# ozino_xyz_blue.net
KiCad netlist of a schematic drawn in EAGLE
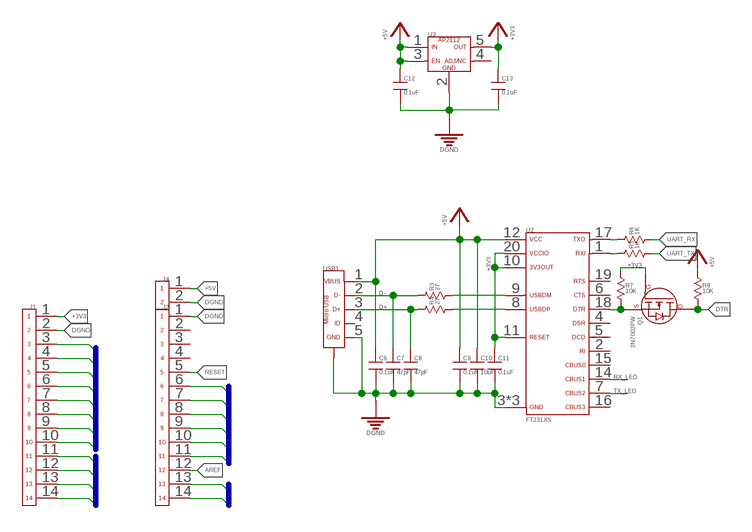
[diagram p0: schematic, sheet 1, part 1 of 2]
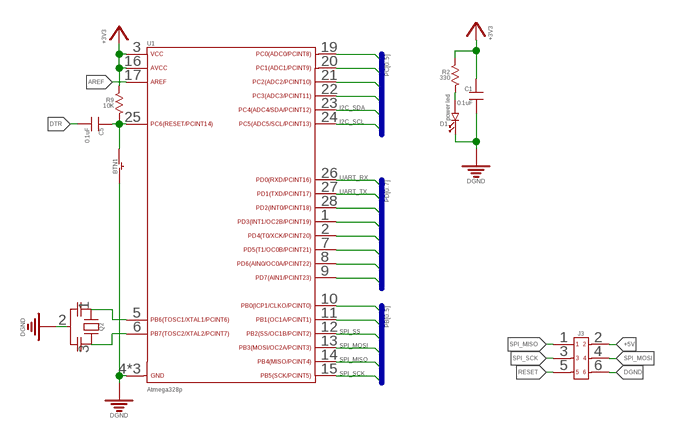
[diagram p1: schematic, sheet 1, part 2 of 2]

(export (version "E")
  (design (tool "Eeschema 10.0.6"))
  (components
    (comp (ref "BTN1")
      (value "BTN_NORMAL_OFF_6_3.5_SMD")
      (footprint "eagle-import:BTN_6_3.5_SMD")
      (libsource (lib "eagle-import") (part "BTN_NORMAL_OFF_6_3.5_SMD"))
    )
    (comp (ref "C1")
      (value "0.1uF")
      (footprint "eagle-import:0402")
      (libsource (lib "eagle-import") (part "CAPACITOR_FIXED_0402"))
    )
    (comp (ref "C5")
      (value "0.1uF")
      (footprint "eagle-import:0402")
      (libsource (lib "eagle-import") (part "CAPACITOR_FIXED_0402"))
    )
    (comp (ref "C6")
      (value "0.1uF")
      (footprint "eagle-import:0402")
      (libsource (lib "eagle-import") (part "CAPACITOR_FIXED_0402"))
    )
    (comp (ref "C7")
      (value "47pF")
      (footprint "eagle-import:0402")
      (libsource (lib "eagle-import") (part "CAPACITOR_FIXED_0402"))
    )
    (comp (ref "C8")
      (value "47pF")
      (footprint "eagle-import:0402")
      (libsource (lib "eagle-import") (part "CAPACITOR_FIXED_0402"))
    )
    (comp (ref "C9")
      (value "0.1uF")
      (footprint "eagle-import:0402")
      (libsource (lib "eagle-import") (part "CAPACITOR_FIXED_0402"))
    )
    (comp (ref "C10")
      (value "10uF")
      (footprint "eagle-import:0402")
      (libsource (lib "eagle-import") (part "CAPACITOR_FIXED_0402"))
    )
    (comp (ref "C11")
      (value "0.1uF")
      (footprint "eagle-import:0402")
      (libsource (lib "eagle-import") (part "CAPACITOR_FIXED_0402"))
    )
    (comp (ref "C12")
      (value "0.1uF")
      (footprint "eagle-import:0402")
      (libsource (lib "eagle-import") (part "CAPACITOR_FIXED_0402"))
    )
    (comp (ref "C13")
      (value "0.1uF")
      (footprint "eagle-import:0402")
      (libsource (lib "eagle-import") (part "CAPACITOR_FIXED_0402"))
    )
    (comp (ref "D1")
      (value "power led")
      (footprint "eagle-import:0805DIODE")
      (libsource (lib "eagle-import") (part "LED-0805"))
    )
    (comp (ref "J1")
      (value "14PIN_HEADER_PITCH2.54MM_TH")
      (footprint "eagle-import:14PIN_HEADER_PITCH2.54MM_TH")
      (libsource (lib "eagle-import") (part "14PIN_HEADER_PITCH2.54MM_TH"))
    )
    (comp (ref "J2")
      (value "14PIN_HEADER_PITCH2.54MM_TH")
      (footprint "eagle-import:14PIN_HEADER_PITCH2.54MM_TH")
      (libsource (lib "eagle-import") (part "14PIN_HEADER_PITCH2.54MM_TH"))
    )
    (comp (ref "J3")
      (value "6PIN_2ROW_TC2030_NL")
      (footprint "eagle-import:TC2030_NL")
      (libsource (lib "eagle-import") (part "6PIN_2ROW_TC2030_NL"))
    )
    (comp (ref "J4")
      (value "2PIN_HEADER_PITCH2.54MM_TH")
      (footprint "eagle-import:2PIN_HEADER_PITCH2.54MM_TH")
      (libsource (lib "eagle-import") (part "2PIN_HEADER_PITCH2.54MM_TH"))
    )
    (comp (ref "Q1")
      (value "2N7002PW")
      (footprint "eagle-import:SOT323(SC-70)")
      (libsource (lib "eagle-import") (part "2N7002PW"))
    )
    (comp (ref "Q2")
      (value "RESONATORS")
      (footprint "eagle-import:CXTCE_____V")
      (libsource (lib "eagle-import") (part "RESONATORS"))
    )
    (comp (ref "R2")
      (value "330")
      (footprint "eagle-import:0805")
      (libsource (lib "eagle-import") (part "RESISTOR_0805"))
    )
    (comp (ref "R3")
      (value "27")
      (footprint "eagle-import:0402")
      (libsource (lib "eagle-import") (part "RESISTOR_0402"))
    )
    (comp (ref "R4")
      (value "27")
      (footprint "eagle-import:0402")
      (libsource (lib "eagle-import") (part "RESISTOR_0402"))
    )
    (comp (ref "R5")
      (value "1K")
      (footprint "eagle-import:0402")
      (libsource (lib "eagle-import") (part "RESISTOR_0402"))
    )
    (comp (ref "R6")
      (value "1K")
      (footprint "eagle-import:0402")
      (libsource (lib "eagle-import") (part "RESISTOR_0402"))
    )
    (comp (ref "R7")
      (value "10K")
      (footprint "eagle-import:0402")
      (libsource (lib "eagle-import") (part "RESISTOR_0402"))
    )
    (comp (ref "R8")
      (value "10K")
      (footprint "eagle-import:0402")
      (libsource (lib "eagle-import") (part "RESISTOR_0402"))
    )
    (comp (ref "R9")
      (value "10K")
      (footprint "eagle-import:0402")
      (libsource (lib "eagle-import") (part "RESISTOR_0402"))
    )
    (comp (ref "U1")
      (value "Atmega328p")
      (footprint "eagle-import:QFN-28")
      (libsource (lib "eagle-import") (part "ATMEGA48A/PA/88A/PA/168A/PA/328/P(28PIN)_28QFN"))
    )
    (comp (ref "U2")
      (value "FT231XS_WFQFN20")
      (footprint "eagle-import:WFQFN-20")
      (libsource (lib "eagle-import") (part "FT231XS_WFQFN20"))
    )
    (comp (ref "U3")
      (value "AP2112K_SOT-23-5")
      (footprint "eagle-import:SOT-23-5")
      (libsource (lib "eagle-import") (part "AP2112K_SOT-23-5"))
    )
    (comp (ref "USB1")
      (value "USB-2.0-MICRO_SMD_SMD")
      (footprint "eagle-import:MICRO-USB-B-SMD-SMD")
      (libsource (lib "eagle-import") (part "USB-2.0-MICRO_SMD_SMD"))
    )
  )
  (nets
    (net (code "9") (name "+3V3") (class "Default")
      (node (ref "C1") (pin "1") (pinfunction "1_1") (pintype "passive"))
      (node (ref "C11") (pin "1") (pinfunction "1_1") (pintype "passive"))
      (node (ref "C13") (pin "1") (pinfunction "1_1") (pintype "passive"))
      (node (ref "J1") (pin "1") (pinfunction "1_1") (pintype "passive"))
      (node (ref "Q1") (pin "1") (pinfunction "G_1") (pintype "passive"))
      (node (ref "R2") (pin "1") (pinfunction "1_1") (pintype "passive"))
      (node (ref "R7") (pin "1") (pinfunction "1_1") (pintype "passive"))
      (node (ref "R9") (pin "1") (pinfunction "1_1") (pintype "passive"))
      (node (ref "U1") (pin "16") (pinfunction "AVCC_16") (pintype "passive"))
      (node (ref "U1") (pin "3") (pinfunction "VCC_3") (pintype "passive"))
      (node (ref "U2") (pin "10") (pinfunction "3V3OUT_10") (pintype "passive"))
      (node (ref "U2") (pin "11") (pinfunction "RESET_11") (pintype "passive"))
      (node (ref "U2") (pin "20") (pinfunction "VCCIO_20") (pintype "passive"))
      (node (ref "U3") (pin "5") (pinfunction "5_5") (pintype "passive"))
    )
    (net (code "10") (name "+5V") (class "Default")
      (node (ref "C10") (pin "1") (pinfunction "1_1") (pintype "passive"))
      (node (ref "C12") (pin "1") (pinfunction "1_1") (pintype "passive"))
      (node (ref "C6") (pin "1") (pinfunction "1_1") (pintype "passive"))
      (node (ref "C9") (pin "1") (pinfunction "1_1") (pintype "passive"))
      (node (ref "J3") (pin "2") (pinfunction "2_2") (pintype "passive"))
      (node (ref "J4") (pin "1") (pinfunction "1_1") (pintype "passive"))
      (node (ref "R8") (pin "1") (pinfunction "1_1") (pintype "passive"))
      (node (ref "U2") (pin "12") (pinfunction "VCC_12") (pintype "passive"))
      (node (ref "U3") (pin "1") (pinfunction "1_1") (pintype "passive"))
      (node (ref "U3") (pin "3") (pinfunction "3_3") (pintype "passive"))
      (node (ref "USB1") (pin "1") (pinfunction "VBUS_1") (pintype "passive"))
    )
    (net (code "11") (name "/D+") (class "Default")
      (node (ref "C8") (pin "1") (pinfunction "1_1") (pintype "passive"))
      (node (ref "R4") (pin "1") (pinfunction "1_1") (pintype "passive"))
      (node (ref "USB1") (pin "3") (pinfunction "D+_3") (pintype "passive"))
    )
    (net (code "12") (name "/D-") (class "Default")
      (node (ref "C7") (pin "1") (pinfunction "1_1") (pintype "passive"))
      (node (ref "R3") (pin "1") (pinfunction "1_1") (pintype "passive"))
      (node (ref "USB1") (pin "2") (pinfunction "D-_2") (pintype "passive"))
    )
    (net (code "13") (name "/I2C_SCL") (class "Default")
      (node (ref "J2") (pin "6") (pinfunction "6_6") (pintype "passive"))
      (node (ref "U1") (pin "24") (pinfunction "PC5_24") (pintype "passive"))
    )
    (net (code "14") (name "/I2C_SDA") (class "Default")
      (node (ref "J2") (pin "7") (pinfunction "7_7") (pintype "passive"))
      (node (ref "U1") (pin "23") (pinfunction "PC4_23") (pintype "passive"))
    )
    (net (code "15") (name "/PB0") (class "Default")
      (node (ref "J1") (pin "11") (pinfunction "11_11") (pintype "passive"))
      (node (ref "U1") (pin "10") (pinfunction "PB0_10") (pintype "passive"))
    )
    (net (code "16") (name "/PB1") (class "Default")
      (node (ref "J1") (pin "12") (pinfunction "12_12") (pintype "passive"))
      (node (ref "U1") (pin "11") (pinfunction "PB1_11") (pintype "passive"))
    )
    (net (code "18") (name "/PC0") (class "Default")
      (node (ref "J2") (pin "11") (pinfunction "11_11") (pintype "passive"))
      (node (ref "U1") (pin "19") (pinfunction "PC0_19") (pintype "passive"))
    )
    (net (code "19") (name "/PC1") (class "Default")
      (node (ref "J2") (pin "10") (pinfunction "10_10") (pintype "passive"))
      (node (ref "U1") (pin "20") (pinfunction "PC1_20") (pintype "passive"))
    )
    (net (code "20") (name "/PC2") (class "Default")
      (node (ref "J2") (pin "9") (pinfunction "9_9") (pintype "passive"))
      (node (ref "U1") (pin "21") (pinfunction "PC2_21") (pintype "passive"))
    )
    (net (code "21") (name "/PC3") (class "Default")
      (node (ref "J2") (pin "8") (pinfunction "8_8") (pintype "passive"))
      (node (ref "U1") (pin "22") (pinfunction "PC3_22") (pintype "passive"))
    )
    (net (code "23") (name "/PD2") (class "Default")
      (node (ref "J1") (pin "5") (pinfunction "5_5") (pintype "passive"))
      (node (ref "U1") (pin "28") (pinfunction "PD2_28") (pintype "passive"))
    )
    (net (code "24") (name "/PD3") (class "Default")
      (node (ref "J1") (pin "6") (pinfunction "6_6") (pintype "passive"))
      (node (ref "U1") (pin "1") (pinfunction "PD3_1") (pintype "passive"))
    )
    (net (code "25") (name "/PD4") (class "Default")
      (node (ref "J1") (pin "7") (pinfunction "7_7") (pintype "passive"))
      (node (ref "U1") (pin "2") (pinfunction "PD4_2") (pintype "passive"))
    )
    (net (code "26") (name "/PD5") (class "Default")
      (node (ref "J1") (pin "8") (pinfunction "8_8") (pintype "passive"))
      (node (ref "U1") (pin "7") (pinfunction "PD5_7") (pintype "passive"))
    )
    (net (code "27") (name "/PD6") (class "Default")
      (node (ref "J1") (pin "9") (pinfunction "9_9") (pintype "passive"))
      (node (ref "U1") (pin "8") (pinfunction "PD6_8") (pintype "passive"))
    )
    (net (code "28") (name "/PD7") (class "Default")
      (node (ref "J1") (pin "10") (pinfunction "10_10") (pintype "passive"))
      (node (ref "U1") (pin "9") (pinfunction "PD7_9") (pintype "passive"))
    )
    (net (code "30") (name "/RX_LED") (class "Default")
      (node (ref "U2") (pin "14") (pinfunction "CBUS1_14") (pintype "passive"))
    )
    (net (code "31") (name "/SPI_SS") (class "Default")
      (node (ref "J1") (pin "13") (pinfunction "13_13") (pintype "passive"))
      (node (ref "U1") (pin "12") (pinfunction "PB2_12") (pintype "passive"))
    )
    (net (code "32") (name "/TX_LED") (class "Default")
      (node (ref "U2") (pin "7") (pinfunction "CBUS2_7") (pintype "passive"))
    )
    (net (code "33") (name "AREF") (class "Default")
      (node (ref "J2") (pin "12") (pinfunction "12_12") (pintype "passive"))
      (node (ref "U1") (pin "17") (pinfunction "AREF_17") (pintype "passive"))
    )
    (net (code "34") (name "DGND") (class "Default")
      (node (ref "BTN1") (pin "1") (pinfunction "1_1") (pintype "passive"))
      (node (ref "C1") (pin "2") (pinfunction "2_2") (pintype "passive"))
      (node (ref "C10") (pin "2") (pinfunction "2_2") (pintype "passive"))
      (node (ref "C11") (pin "2") (pinfunction "2_2") (pintype "passive"))
      (node (ref "C12") (pin "2") (pinfunction "2_2") (pintype "passive"))
      (node (ref "C13") (pin "2") (pinfunction "2_2") (pintype "passive"))
      (node (ref "C6") (pin "2") (pinfunction "2_2") (pintype "passive"))
      (node (ref "C7") (pin "2") (pinfunction "2_2") (pintype "passive"))
      (node (ref "C8") (pin "2") (pinfunction "2_2") (pintype "passive"))
      (node (ref "C9") (pin "2") (pinfunction "2_2") (pintype "passive"))
      (node (ref "D1") (pin "1") (pinfunction "K_1") (pintype "passive"))
      (node (ref "J1") (pin "2") (pinfunction "2_2") (pintype "passive"))
      (node (ref "J2") (pin "1") (pinfunction "1_1") (pintype "passive"))
      (node (ref "J3") (pin "6") (pinfunction "6_6") (pintype "passive"))
      (node (ref "J4") (pin "2") (pinfunction "2_2") (pintype "passive"))
      (node (ref "Q2") (pin "2") (pinfunction "2_2") (pintype "passive"))
      (node (ref "U1") (pin "18") (pinfunction "GND_18") (pintype "passive"))
      (node (ref "U1") (pin "4") (pinfunction "GND_4") (pintype "passive"))
      (node (ref "U1") (pin "T") (pinfunction "GND_T") (pintype "passive"))
      (node (ref "U2") (pin "13") (pinfunction "GND_13") (pintype "passive"))
      (node (ref "U2") (pin "3") (pinfunction "GND_3") (pintype "passive"))
      (node (ref "U2") (pin "T") (pinfunction "GND_T") (pintype "passive"))
      (node (ref "U3") (pin "2") (pinfunction "2_2") (pintype "passive"))
      (node (ref "USB1") (pin "5") (pinfunction "GND_5") (pintype "passive"))
      (node (ref "USB1") (pin "M1") (pinfunction "SHIELD_M1") (pintype "passive"))
      (node (ref "USB1") (pin "M2") (pinfunction "SHIELD_M2") (pintype "passive"))
      (node (ref "USB1") (pin "M3") (pinfunction "SHIELD_M3") (pintype "passive"))
      (node (ref "USB1") (pin "M4") (pinfunction "SHIELD_M4") (pintype "passive"))
      (node (ref "USB1") (pin "S1") (pinfunction "SHIELD_S1") (pintype "passive"))
      (node (ref "USB1") (pin "S2") (pinfunction "SHIELD_S2") (pintype "passive"))
    )
    (net (code "35") (name "DTR") (class "Default")
      (node (ref "C5") (pin "2") (pinfunction "2_2") (pintype "passive"))
      (node (ref "Q1") (pin "3") (pinfunction "D_3") (pintype "passive"))
      (node (ref "R8") (pin "2") (pinfunction "2_2") (pintype "passive"))
    )
    (net (code "36") (name "Net-(D1-A)") (class "Default")
      (node (ref "D1") (pin "2") (pinfunction "A_2") (pintype "passive"))
      (node (ref "R2") (pin "2") (pinfunction "2_2") (pintype "passive"))
    )
    (net (code "37") (name "Net-(Q1-S)") (class "Default")
      (node (ref "Q1") (pin "2") (pinfunction "S_2") (pintype "passive"))
      (node (ref "R7") (pin "2") (pinfunction "2_2") (pintype "passive"))
      (node (ref "U2") (pin "18") (pinfunction "DTR_18") (pintype "passive"))
    )
    (net (code "38") (name "Net-(U1-PB6)") (class "Default")
      (node (ref "Q2") (pin "1") (pinfunction "1_1") (pintype "passive"))
      (node (ref "U1") (pin "5") (pinfunction "PB6_5") (pintype "passive"))
    )
    (net (code "39") (name "Net-(U1-PB7)") (class "Default")
      (node (ref "Q2") (pin "3") (pinfunction "3_3") (pintype "passive"))
      (node (ref "U1") (pin "6") (pinfunction "PB7_6") (pintype "passive"))
    )
    (net (code "40") (name "Net-(U2-RXD)") (class "Default")
      (node (ref "R5") (pin "1") (pinfunction "1_1") (pintype "passive"))
      (node (ref "U2") (pin "1") (pinfunction "RXD_1") (pintype "passive"))
    )
    (net (code "41") (name "Net-(U2-TXD)") (class "Default")
      (node (ref "R6") (pin "1") (pinfunction "1_1") (pintype "passive"))
      (node (ref "U2") (pin "17") (pinfunction "TXD_17") (pintype "passive"))
    )
    (net (code "42") (name "Net-(U2-USBDM)") (class "Default")
      (node (ref "R3") (pin "2") (pinfunction "2_2") (pintype "passive"))
      (node (ref "U2") (pin "9") (pinfunction "USBDM_9") (pintype "passive"))
    )
    (net (code "43") (name "Net-(U2-USBDP)") (class "Default")
      (node (ref "R4") (pin "2") (pinfunction "2_2") (pintype "passive"))
      (node (ref "U2") (pin "8") (pinfunction "USBDP_8") (pintype "passive"))
    )
    (net (code "44") (name "RESET") (class "Default")
      (node (ref "BTN1") (pin "2") (pinfunction "2_2") (pintype "passive"))
      (node (ref "C5") (pin "1") (pinfunction "1_1") (pintype "passive"))
      (node (ref "J2") (pin "5") (pinfunction "5_5") (pintype "passive"))
      (node (ref "J3") (pin "5") (pinfunction "5_5") (pintype "passive"))
      (node (ref "R9") (pin "2") (pinfunction "2_2") (pintype "passive"))
      (node (ref "U1") (pin "25") (pinfunction "PC6_25") (pintype "passive"))
    )
    (net (code "45") (name "SPI_MISO") (class "Default")
      (node (ref "J2") (pin "14") (pinfunction "14_14") (pintype "passive"))
      (node (ref "J3") (pin "1") (pinfunction "1_1") (pintype "passive"))
      (node (ref "U1") (pin "14") (pinfunction "PB4_14") (pintype "passive"))
    )
    (net (code "46") (name "SPI_MOSI") (class "Default")
      (node (ref "J1") (pin "14") (pinfunction "14_14") (pintype "passive"))
      (node (ref "J3") (pin "4") (pinfunction "4_4") (pintype "passive"))
      (node (ref "U1") (pin "13") (pinfunction "PB3_13") (pintype "passive"))
    )
    (net (code "47") (name "SPI_SCK") (class "Default")
      (node (ref "J2") (pin "13") (pinfunction "13_13") (pintype "passive"))
      (node (ref "J3") (pin "3") (pinfunction "3_3") (pintype "passive"))
      (node (ref "U1") (pin "15") (pinfunction "PB5_15") (pintype "passive"))
    )
    (net (code "48") (name "UART_RX") (class "Default")
      (node (ref "J1") (pin "3") (pinfunction "3_3") (pintype "passive"))
      (node (ref "R6") (pin "2") (pinfunction "2_2") (pintype "passive"))
      (node (ref "U1") (pin "26") (pinfunction "PD0_26") (pintype "passive"))
    )
    (net (code "49") (name "UART_TX") (class "Default")
      (node (ref "J1") (pin "4") (pinfunction "4_4") (pintype "passive"))
      (node (ref "R5") (pin "2") (pinfunction "2_2") (pintype "passive"))
      (node (ref "U1") (pin "27") (pinfunction "PD1_27") (pintype "passive"))
    )
    (net (code "50") (name "unconnected-(J2-Pad2)") (class "Default")
      (node (ref "J2") (pin "2") (pinfunction "2_2") (pintype "passive"))
    )
    (net (code "51") (name "unconnected-(J2-Pad3)") (class "Default")
      (node (ref "J2") (pin "3") (pinfunction "3_3") (pintype "passive"))
    )
    (net (code "52") (name "unconnected-(J2-Pad4)") (class "Default")
      (node (ref "J2") (pin "4") (pinfunction "4_4") (pintype "passive"))
    )
    (net (code "53") (name "unconnected-(U2-CBUS0-Pad15)") (class "Default")
      (node (ref "U2") (pin "15") (pinfunction "CBUS0_15") (pintype "passive"))
    )
    (net (code "54") (name "unconnected-(U2-CBUS3-Pad16)") (class "Default")
      (node (ref "U2") (pin "16") (pinfunction "CBUS3_16") (pintype "passive"))
    )
    (net (code "55") (name "unconnected-(U2-CTS-Pad6)") (class "Default")
      (node (ref "U2") (pin "6") (pinfunction "CTS_6") (pintype "passive"))
    )
    (net (code "56") (name "unconnected-(U2-DCD-Pad5)") (class "Default")
      (node (ref "U2") (pin "5") (pinfunction "DCD_5") (pintype "passive"))
    )
    (net (code "57") (name "unconnected-(U2-DSR-Pad4)") (class "Default")
      (node (ref "U2") (pin "4") (pinfunction "DSR_4") (pintype "passive"))
    )
    (net (code "58") (name "unconnected-(U2-RI-Pad2)") (class "Default")
      (node (ref "U2") (pin "2") (pinfunction "RI_2") (pintype "passive"))
    )
    (net (code "59") (name "unconnected-(U2-RTS-Pad19)") (class "Default")
      (node (ref "U2") (pin "19") (pinfunction "RTS_19") (pintype "passive"))
    )
    (net (code "60") (name "unconnected-(U3-Pad4)") (class "Default")
      (node (ref "U3") (pin "4") (pinfunction "4_4") (pintype "passive"))
    )
    (net (code "61") (name "unconnected-(USB1-ID-Pad4)") (class "Default")
      (node (ref "USB1") (pin "4") (pinfunction "ID_4") (pintype "passive"))
    )
  )
)
